# LEDDriver.net
KiCad netlist of a schematic drawn in Altium Designer
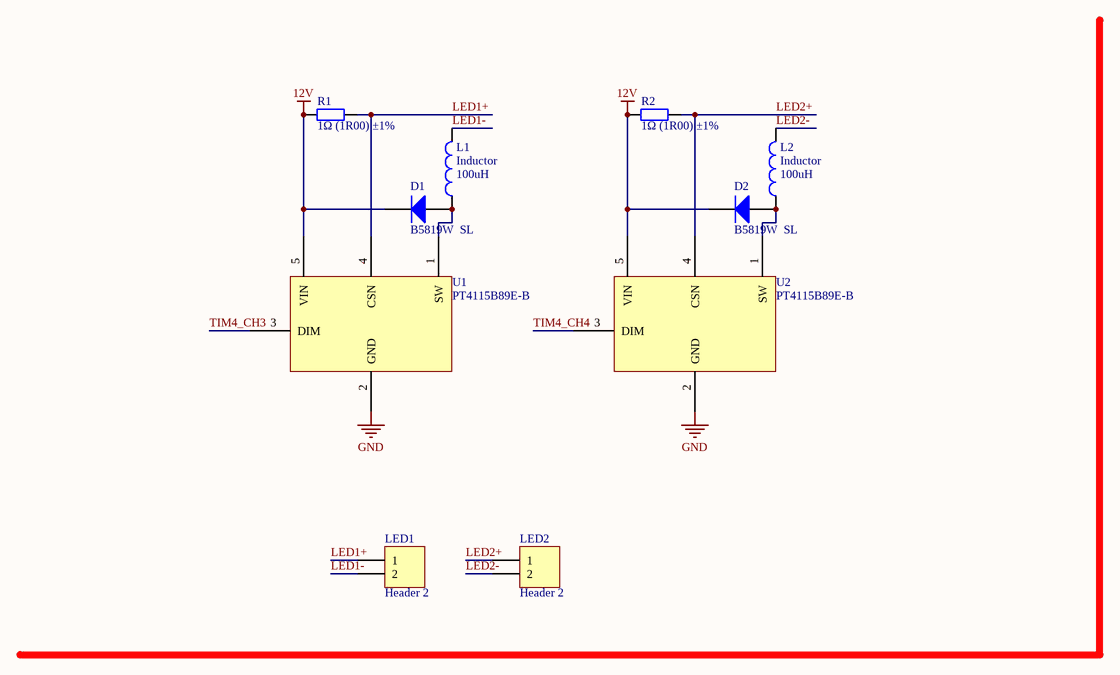
[diagram p0: LEDDriver.SchDoc]

(export (version "E")
  (design (tool "Eeschema 10.0.6"))
  (components
    (comp (ref "D1")
      (value "B5819W  SL")
      (footprint "SOD-123")
      (description "肖特基二极管")
      (libsource (lib "Miscellaneous Devices LC") (part "SOD-123 B5819W  SL"))
    )
    (comp (ref "D2")
      (value "B5819W  SL")
      (footprint "SOD-123")
      (description "肖特基二极管")
      (libsource (lib "Miscellaneous Devices LC") (part "SOD-123 B5819W  SL"))
    )
    (comp (ref "L1")
      (value "Inductor")
      (footprint "L0630(6x7x3)")
      (fields (field (name "ALTIUM_VALUE") "100uH") (field (name "PUBLISHER") "Altium Limited"))
      (libsource (lib "Miscellaneous Devices") (part "Inductor"))
    )
    (comp (ref "L2")
      (value "Inductor")
      (footprint "L0630(6x7x3)")
      (fields (field (name "ALTIUM_VALUE") "100uH") (field (name "PUBLISHER") "Altium Limited"))
      (libsource (lib "Miscellaneous Devices") (part "Inductor"))
    )
    (comp (ref "LED1")
      (value "Header 2")
      (footprint "XH2.54_2P")
      (description "Header, 2-Pin")
      (fields (field (name "PUBLISHER") "Altium Limited"))
      (libsource (lib "Miscellaneous Connectors") (part "Header 2"))
    )
    (comp (ref "LED2")
      (value "Header 2")
      (footprint "XH2.54_2P")
      (description "Header, 2-Pin")
      (fields (field (name "PUBLISHER") "Altium Limited"))
      (libsource (lib "Miscellaneous Connectors") (part "Header 2"))
    )
    (comp (ref "R1")
      (value "1Ω (1R00) ±1%")
      (footprint "1206_R")
      (description "贴片电阻")
      (libsource (lib "Miscellaneous Devices LC") (part "1206 1Ω (1R00) 1%"))
    )
    (comp (ref "R2")
      (value "1Ω (1R00) ±1%")
      (footprint "1206_R")
      (description "贴片电阻")
      (libsource (lib "Miscellaneous Devices LC") (part "1206 1Ω (1R00) 1%"))
    )
    (comp (ref "U1")
      (value "PT4115B89E-B")
      (footprint "SOT89-150P420X160-5M")
      (libsource (lib "PT4115B89E-B") (part "PT4115B89E-B"))
    )
    (comp (ref "U2")
      (value "PT4115B89E-B")
      (footprint "SOT89-150P420X160-5M")
      (libsource (lib "PT4115B89E-B") (part "PT4115B89E-B"))
    )
  )
  (nets
    (net (code "1") (name "/LED1+") (class "Default")
      (node (ref "LED1") (pin "1") (pinfunction "1_1") (pintype "passive"))
      (node (ref "R1") (pin "2") (pinfunction "2_2") (pintype "passive"))
      (node (ref "U1") (pin "4") (pinfunction "CSN_4") (pintype "passive"))
    )
    (net (code "2") (name "/LED1-") (class "Default")
      (node (ref "L1") (pin "2") (pinfunction "2_2") (pintype "passive"))
      (node (ref "LED1") (pin "2") (pinfunction "2_2") (pintype "passive"))
    )
    (net (code "3") (name "/LED2+") (class "Default")
      (node (ref "LED2") (pin "1") (pinfunction "1_1") (pintype "passive"))
      (node (ref "R2") (pin "2") (pinfunction "2_2") (pintype "passive"))
      (node (ref "U2") (pin "4") (pinfunction "CSN_4") (pintype "passive"))
    )
    (net (code "4") (name "/LED2-") (class "Default")
      (node (ref "L2") (pin "2") (pinfunction "2_2") (pintype "passive"))
      (node (ref "LED2") (pin "2") (pinfunction "2_2") (pintype "passive"))
    )
    (net (code "5") (name "/TIM4_CH3") (class "Default")
      (node (ref "U1") (pin "3") (pinfunction "DIM_3") (pintype "passive"))
    )
    (net (code "6") (name "/TIM4_CH4") (class "Default")
      (node (ref "U2") (pin "3") (pinfunction "DIM_3") (pintype "passive"))
    )
    (net (code "7") (name "12V") (class "Default")
      (node (ref "D1") (pin "2") (pinfunction "K_2") (pintype "passive"))
      (node (ref "D2") (pin "2") (pinfunction "K_2") (pintype "passive"))
      (node (ref "R1") (pin "1") (pinfunction "1_1") (pintype "passive"))
      (node (ref "R2") (pin "1") (pinfunction "1_1") (pintype "passive"))
      (node (ref "U1") (pin "5") (pinfunction "VIN_5") (pintype "passive"))
      (node (ref "U2") (pin "5") (pinfunction "VIN_5") (pintype "passive"))
    )
    (net (code "8") (name "GND") (class "Default")
      (node (ref "U1") (pin "2") (pinfunction "GND_2") (pintype "passive"))
      (node (ref "U2") (pin "2") (pinfunction "GND_2") (pintype "passive"))
    )
    (net (code "9") (name "Net-(D1-A)") (class "Default")
      (node (ref "D1") (pin "1") (pinfunction "A_1") (pintype "passive"))
      (node (ref "L1") (pin "1") (pinfunction "1_1") (pintype "passive"))
      (node (ref "U1") (pin "1") (pinfunction "SW_1") (pintype "passive"))
    )
    (net (code "10") (name "Net-(D2-A)") (class "Default")
      (node (ref "D2") (pin "1") (pinfunction "A_1") (pintype "passive"))
      (node (ref "L2") (pin "1") (pinfunction "1_1") (pintype "passive"))
      (node (ref "U2") (pin "1") (pinfunction "SW_1") (pintype "passive"))
    )
  )
)
